# 2732Adapter.net
KiCad netlist of a schematic drawn in EAGLE
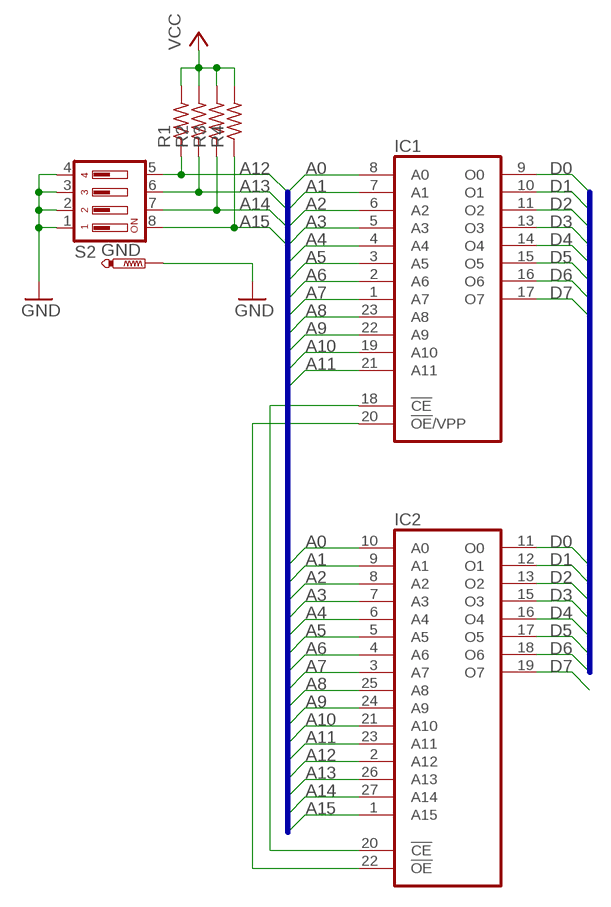
[diagram p0: schematic, sheet 1]

(export (version "E")
  (design (tool "Eeschema 10.0.6"))
  (components
    (comp (ref "GND")
      (value "PTR1B1,27")
      (footprint "eagle-import:B1,27")
      (libsource (lib "eagle-import") (part "PTR1B1,27"))
    )
    (comp (ref "IC1")
      (value "2732")
      (footprint "eagle-import:DIL24")
      (libsource (lib "eagle-import") (part "2732"))
    )
    (comp (ref "IC2")
      (value "27512")
      (footprint "eagle-import:DIL28")
      (libsource (lib "eagle-import") (part "27512"))
    )
    (comp (ref "R1")
      (value "R-US_0204/5")
      (footprint "eagle-import:0204_5")
      (libsource (lib "eagle-import") (part "R-US_0204/5"))
    )
    (comp (ref "R2")
      (value "R-US_0204/5")
      (footprint "eagle-import:0204_5")
      (libsource (lib "eagle-import") (part "R-US_0204/5"))
    )
    (comp (ref "R3")
      (value "R-US_0204/5")
      (footprint "eagle-import:0204_5")
      (libsource (lib "eagle-import") (part "R-US_0204/5"))
    )
    (comp (ref "R4")
      (value "R-US_0204/5")
      (footprint "eagle-import:0204_5")
      (libsource (lib "eagle-import") (part "R-US_0204/5"))
    )
    (comp (ref "S2")
      (value "DP04")
      (footprint "eagle-import:DP-04")
      (libsource (lib "eagle-import") (part "DP04"))
    )
  )
  (nets
    (net (code "1") (name "/A0") (class "Default")
      (node (ref "IC1") (pin "8") (pinfunction "A0_8") (pintype "input"))
      (node (ref "IC2") (pin "10") (pinfunction "A0_10") (pintype "input"))
    )
    (net (code "2") (name "/A1") (class "Default")
      (node (ref "IC1") (pin "7") (pinfunction "A1_7") (pintype "input"))
      (node (ref "IC2") (pin "9") (pinfunction "A1_9") (pintype "input"))
    )
    (net (code "3") (name "/A2") (class "Default")
      (node (ref "IC1") (pin "6") (pinfunction "A2_6") (pintype "input"))
      (node (ref "IC2") (pin "8") (pinfunction "A2_8") (pintype "input"))
    )
    (net (code "4") (name "/A3") (class "Default")
      (node (ref "IC1") (pin "5") (pinfunction "A3_5") (pintype "input"))
      (node (ref "IC2") (pin "7") (pinfunction "A3_7") (pintype "input"))
    )
    (net (code "5") (name "/A4") (class "Default")
      (node (ref "IC1") (pin "4") (pinfunction "A4_4") (pintype "input"))
      (node (ref "IC2") (pin "6") (pinfunction "A4_6") (pintype "input"))
    )
    (net (code "6") (name "/A5") (class "Default")
      (node (ref "IC1") (pin "3") (pinfunction "A5_3") (pintype "input"))
      (node (ref "IC2") (pin "5") (pinfunction "A5_5") (pintype "input"))
    )
    (net (code "7") (name "/A6") (class "Default")
      (node (ref "IC1") (pin "2") (pinfunction "A6_2") (pintype "input"))
      (node (ref "IC2") (pin "4") (pinfunction "A6_4") (pintype "input"))
    )
    (net (code "8") (name "/A7") (class "Default")
      (node (ref "IC1") (pin "1") (pinfunction "A7_1") (pintype "input"))
      (node (ref "IC2") (pin "3") (pinfunction "A7_3") (pintype "input"))
    )
    (net (code "9") (name "/A8") (class "Default")
      (node (ref "IC1") (pin "23") (pinfunction "A8_23") (pintype "input"))
      (node (ref "IC2") (pin "25") (pinfunction "A8_25") (pintype "input"))
    )
    (net (code "10") (name "/A9") (class "Default")
      (node (ref "IC1") (pin "22") (pinfunction "A9_22") (pintype "input"))
      (node (ref "IC2") (pin "24") (pinfunction "A9_24") (pintype "input"))
    )
    (net (code "11") (name "/A10") (class "Default")
      (node (ref "IC1") (pin "19") (pinfunction "A10_19") (pintype "input"))
      (node (ref "IC2") (pin "21") (pinfunction "A10_21") (pintype "input"))
    )
    (net (code "12") (name "/A11") (class "Default")
      (node (ref "IC1") (pin "21") (pinfunction "A11_21") (pintype "input"))
      (node (ref "IC2") (pin "23") (pinfunction "A11_23") (pintype "input"))
    )
    (net (code "13") (name "/A12") (class "Default")
      (node (ref "IC2") (pin "2") (pinfunction "A12_2") (pintype "input"))
      (node (ref "R1") (pin "1") (pinfunction "1_1") (pintype "passive"))
      (node (ref "S2") (pin "5") (pinfunction "5_5") (pintype "passive"))
    )
    (net (code "14") (name "/A13") (class "Default")
      (node (ref "IC2") (pin "26") (pinfunction "A13_26") (pintype "input"))
      (node (ref "R2") (pin "1") (pinfunction "1_1") (pintype "passive"))
      (node (ref "S2") (pin "6") (pinfunction "6_6") (pintype "passive"))
    )
    (net (code "15") (name "/A14") (class "Default")
      (node (ref "IC2") (pin "27") (pinfunction "A14_27") (pintype "input"))
      (node (ref "R3") (pin "1") (pinfunction "1_1") (pintype "passive"))
      (node (ref "S2") (pin "7") (pinfunction "7_7") (pintype "passive"))
    )
    (net (code "16") (name "/A15") (class "Default")
      (node (ref "IC2") (pin "1") (pinfunction "A15_1") (pintype "input"))
      (node (ref "R4") (pin "1") (pinfunction "1_1") (pintype "passive"))
      (node (ref "S2") (pin "8") (pinfunction "8_8") (pintype "passive"))
    )
    (net (code "17") (name "/D0") (class "Default")
      (node (ref "IC1") (pin "9") (pinfunction "O0_9") (pintype "tri_state"))
      (node (ref "IC2") (pin "11") (pinfunction "O0_11") (pintype "tri_state"))
    )
    (net (code "18") (name "/D1") (class "Default")
      (node (ref "IC1") (pin "10") (pinfunction "O1_10") (pintype "tri_state"))
      (node (ref "IC2") (pin "12") (pinfunction "O1_12") (pintype "tri_state"))
    )
    (net (code "19") (name "/D2") (class "Default")
      (node (ref "IC1") (pin "11") (pinfunction "O2_11") (pintype "tri_state"))
      (node (ref "IC2") (pin "13") (pinfunction "O2_13") (pintype "tri_state"))
    )
    (net (code "20") (name "/D3") (class "Default")
      (node (ref "IC1") (pin "13") (pinfunction "O3_13") (pintype "tri_state"))
      (node (ref "IC2") (pin "15") (pinfunction "O3_15") (pintype "tri_state"))
    )
    (net (code "21") (name "/D4") (class "Default")
      (node (ref "IC1") (pin "14") (pinfunction "O4_14") (pintype "tri_state"))
      (node (ref "IC2") (pin "16") (pinfunction "O4_16") (pintype "tri_state"))
    )
    (net (code "22") (name "/D5") (class "Default")
      (node (ref "IC1") (pin "15") (pinfunction "O5_15") (pintype "tri_state"))
      (node (ref "IC2") (pin "17") (pinfunction "O5_17") (pintype "tri_state"))
    )
    (net (code "23") (name "/D6") (class "Default")
      (node (ref "IC1") (pin "16") (pinfunction "O6_16") (pintype "tri_state"))
      (node (ref "IC2") (pin "18") (pinfunction "O6_18") (pintype "tri_state"))
    )
    (net (code "24") (name "/D7") (class "Default")
      (node (ref "IC1") (pin "17") (pinfunction "O7_17") (pintype "tri_state"))
      (node (ref "IC2") (pin "19") (pinfunction "O7_19") (pintype "tri_state"))
    )
    (net (code "25") (name "GND") (class "Default")
      (node (ref "GND") (pin "TP") (pinfunction "TP_TP") (pintype "input"))
      (node (ref "S2") (pin "1") (pinfunction "1_1") (pintype "passive"))
      (node (ref "S2") (pin "2") (pinfunction "2_2") (pintype "passive"))
      (node (ref "S2") (pin "3") (pinfunction "3_3") (pintype "passive"))
      (node (ref "S2") (pin "4") (pinfunction "4_4") (pintype "passive"))
    )
    (net (code "26") (name "Net-(IC1A-~{CE})") (class "Default")
      (node (ref "IC1") (pin "18") (pinfunction "~{CE}_18") (pintype "input"))
      (node (ref "IC2") (pin "20") (pinfunction "~{CE}_20") (pintype "input"))
    )
    (net (code "27") (name "Net-(IC1A-~{OE}{slash}VPP)") (class "Default")
      (node (ref "IC1") (pin "20") (pinfunction "~{OE}/VPP_20") (pintype "input"))
      (node (ref "IC2") (pin "22") (pinfunction "~{OE}_22") (pintype "input"))
    )
    (net (code "28") (name "VCC") (class "Default")
      (node (ref "R1") (pin "2") (pinfunction "2_2") (pintype "passive"))
      (node (ref "R2") (pin "2") (pinfunction "2_2") (pintype "passive"))
      (node (ref "R3") (pin "2") (pinfunction "2_2") (pintype "passive"))
      (node (ref "R4") (pin "2") (pinfunction "2_2") (pintype "passive"))
    )
  )
)
